# Teensy-Maxuino-Slave-DRV4835.net
KiCad netlist of a schematic drawn in EAGLE
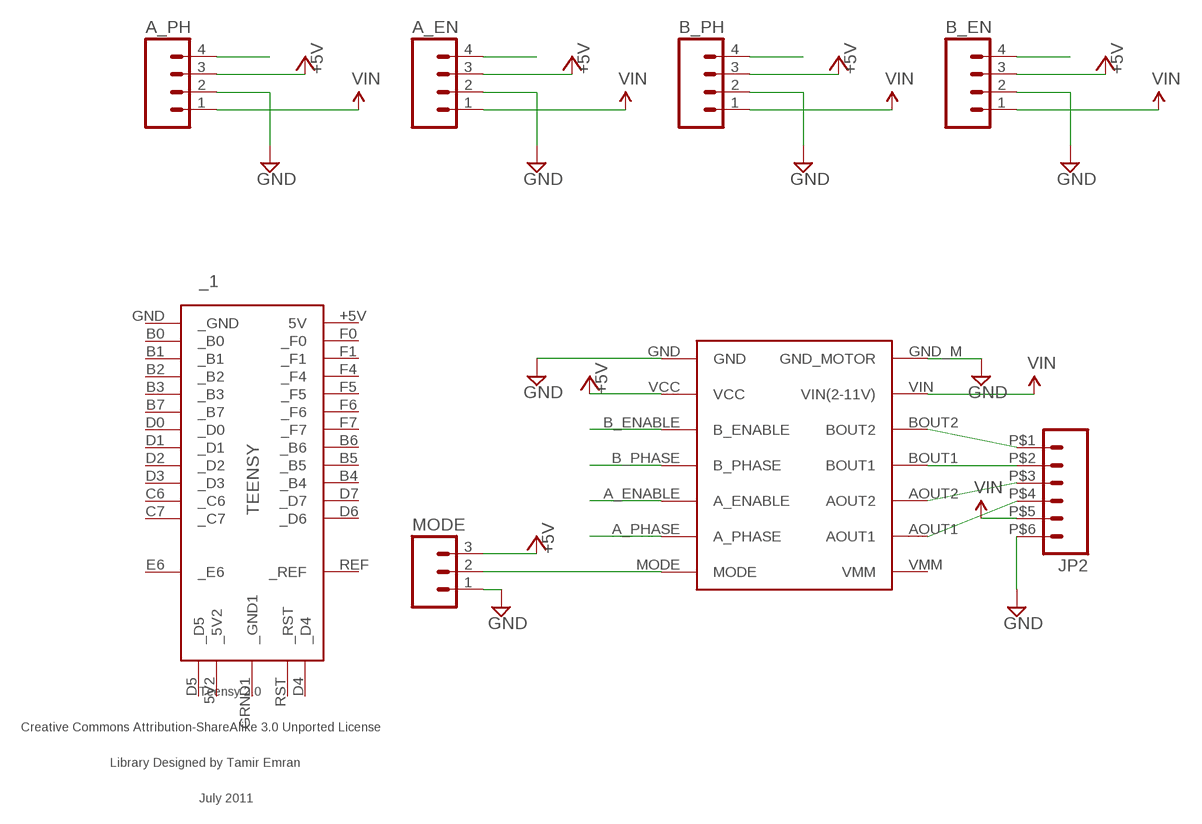
[diagram p0: schematic, sheet 1]

(export (version "E")
  (design (tool "Eeschema 10.0.6"))
  (components
    (comp (ref "A_EN")
      (value "M04PTH")
      (footprint "eagle-import:1X04")
      (libsource (lib "eagle-import") (part "M04PTH"))
    )
    (comp (ref "A_PH")
      (value "M04PTH")
      (footprint "eagle-import:1X04")
      (libsource (lib "eagle-import") (part "M04PTH"))
    )
    (comp (ref "B_EN")
      (value "M04PTH")
      (footprint "eagle-import:1X04")
      (libsource (lib "eagle-import") (part "M04PTH"))
    )
    (comp (ref "B_PH")
      (value "M04PTH")
      (footprint "eagle-import:1X04")
      (libsource (lib "eagle-import") (part "M04PTH"))
    )
    (comp (ref "DRV8835")
      (value "POLOLU_DRV8835")
      (footprint "eagle-import:POLOLU_DRV8835")
      (libsource (lib "eagle-import") (part "POLOLU_DRV8835"))
    )
    (comp (ref "JP2")
      (value "M06")
      (footprint "eagle-import:SPRINGTERMINAL-2.54MM-6")
      (libsource (lib "eagle-import") (part "M06"))
    )
    (comp (ref "MODE")
      (value "M03PTH")
      (footprint "eagle-import:1X03")
      (libsource (lib "eagle-import") (part "M03PTH"))
    )
    (comp (ref "_1")
      (value "TEENSY")
      (footprint "eagle-import:TEENSY")
      (libsource (lib "eagle-import") (part "TEENSY"))
    )
  )
  (nets
    (net (code "1") (name "+5V") (class "Default")
      (node (ref "A_EN") (pin "3") (pinfunction "3_3") (pintype "passive"))
      (node (ref "A_PH") (pin "3") (pinfunction "3_3") (pintype "passive"))
      (node (ref "B_EN") (pin "3") (pinfunction "3_3") (pintype "passive"))
      (node (ref "B_PH") (pin "3") (pinfunction "3_3") (pintype "passive"))
      (node (ref "DRV8835") (pin "VCC") (pinfunction "VCC_VCC") (pintype "bidirectional"))
      (node (ref "MODE") (pin "3") (pinfunction "3_3") (pintype "passive"))
    )
    (net (code "2") (name "/A-ENABLE") (class "Default")
      (node (ref "A_EN") (pin "4") (pinfunction "4_4") (pintype "passive"))
      (node (ref "DRV8835") (pin "A_ENABLE") (pinfunction "A_ENABLE_A_ENABLE") (pintype "bidirectional"))
    )
    (net (code "3") (name "/A-PHASE") (class "Default")
      (node (ref "A_PH") (pin "4") (pinfunction "4_4") (pintype "passive"))
      (node (ref "DRV8835") (pin "A_PHASE") (pinfunction "A_PHASE_A_PHASE") (pintype "bidirectional"))
    )
    (net (code "4") (name "/B-ENABLE") (class "Default")
      (node (ref "B_EN") (pin "4") (pinfunction "4_4") (pintype "passive"))
      (node (ref "DRV8835") (pin "B_ENABLE") (pinfunction "B_ENABLE_B_ENABLE") (pintype "bidirectional"))
    )
    (net (code "5") (name "/B-PHASE") (class "Default")
      (node (ref "B_PH") (pin "4") (pinfunction "4_4") (pintype "passive"))
      (node (ref "DRV8835") (pin "B_PHASE") (pinfunction "B_PHASE_B_PHASE") (pintype "bidirectional"))
    )
    (net (code "6") (name "GND") (class "Default")
      (node (ref "A_EN") (pin "2") (pinfunction "2_2") (pintype "passive"))
      (node (ref "A_PH") (pin "2") (pinfunction "2_2") (pintype "passive"))
      (node (ref "B_EN") (pin "2") (pinfunction "2_2") (pintype "passive"))
      (node (ref "B_PH") (pin "2") (pinfunction "2_2") (pintype "passive"))
      (node (ref "DRV8835") (pin "GND") (pinfunction "GND_GND") (pintype "bidirectional"))
      (node (ref "DRV8835") (pin "GND_M") (pinfunction "GND_MOTOR_GND_M") (pintype "bidirectional"))
      (node (ref "JP2") (pin "P$6") (pinfunction "6_P$6") (pintype "passive"))
      (node (ref "MODE") (pin "1") (pinfunction "1_1") (pintype "passive"))
    )
    (net (code "7") (name "Net-(DRV8835-PadMODE)") (class "Default")
      (node (ref "DRV8835") (pin "MODE") (pinfunction "MODE_MODE") (pintype "bidirectional"))
      (node (ref "MODE") (pin "2") (pinfunction "2_2") (pintype "passive"))
    )
    (net (code "8") (name "Net-(JP2-1)") (class "Default")
      (node (ref "DRV8835") (pin "BOUT2") (pinfunction "BOUT2_BOUT2") (pintype "bidirectional"))
      (node (ref "JP2") (pin "P$1") (pinfunction "1_P$1") (pintype "passive"))
    )
    (net (code "9") (name "Net-(JP2-2)") (class "Default")
      (node (ref "DRV8835") (pin "BOUT1") (pinfunction "BOUT1_BOUT1") (pintype "bidirectional"))
      (node (ref "JP2") (pin "P$2") (pinfunction "2_P$2") (pintype "passive"))
    )
    (net (code "10") (name "Net-(JP2-3)") (class "Default")
      (node (ref "DRV8835") (pin "AOUT2") (pinfunction "AOUT2_AOUT2") (pintype "bidirectional"))
      (node (ref "JP2") (pin "P$3") (pinfunction "3_P$3") (pintype "passive"))
    )
    (net (code "11") (name "Net-(JP2-4)") (class "Default")
      (node (ref "DRV8835") (pin "AOUT1") (pinfunction "AOUT1_AOUT1") (pintype "bidirectional"))
      (node (ref "JP2") (pin "P$4") (pinfunction "4_P$4") (pintype "passive"))
    )
    (net (code "12") (name "VIN") (class "Default")
      (node (ref "A_EN") (pin "1") (pinfunction "1_1") (pintype "passive"))
      (node (ref "A_PH") (pin "1") (pinfunction "1_1") (pintype "passive"))
      (node (ref "B_EN") (pin "1") (pinfunction "1_1") (pintype "passive"))
      (node (ref "B_PH") (pin "1") (pinfunction "1_1") (pintype "passive"))
      (node (ref "DRV8835") (pin "VIN") (pinfunction "VIN(2-11V)_VIN") (pintype "bidirectional"))
      (node (ref "JP2") (pin "P$5") (pinfunction "5_P$5") (pintype "passive"))
    )
    (net (code "13") (name "unconnected-(DRV8835-PadVMM)") (class "Default")
      (node (ref "DRV8835") (pin "VMM") (pinfunction "VMM_VMM") (pintype "bidirectional"))
    )
    (net (code "14") (name "unconnected-(_1-5V-Pad+5V)") (class "Default")
      (node (ref "_1") (pin "+5V") (pinfunction "5V_+5V") (pintype "bidirectional"))
    )
    (net (code "15") (name "unconnected-(_1-_5V2-Pad5V2)") (class "Default")
      (node (ref "_1") (pin "5V2") (pinfunction "_5V2_5V2") (pintype "bidirectional"))
    )
    (net (code "16") (name "unconnected-(_1-_B0-PadB0)") (class "Default")
      (node (ref "_1") (pin "B0") (pinfunction "_B0_B0") (pintype "bidirectional"))
    )
    (net (code "17") (name "unconnected-(_1-_B1-PadB1)") (class "Default")
      (node (ref "_1") (pin "B1") (pinfunction "_B1_B1") (pintype "bidirectional"))
    )
    (net (code "18") (name "unconnected-(_1-_B2-PadB2)") (class "Default")
      (node (ref "_1") (pin "B2") (pinfunction "_B2_B2") (pintype "bidirectional"))
    )
    (net (code "19") (name "unconnected-(_1-_B3-PadB3)") (class "Default")
      (node (ref "_1") (pin "B3") (pinfunction "_B3_B3") (pintype "bidirectional"))
    )
    (net (code "20") (name "unconnected-(_1-_B4-PadB4)") (class "Default")
      (node (ref "_1") (pin "B4") (pinfunction "_B4_B4") (pintype "bidirectional"))
    )
    (net (code "21") (name "unconnected-(_1-_B5-PadB5)") (class "Default")
      (node (ref "_1") (pin "B5") (pinfunction "_B5_B5") (pintype "bidirectional"))
    )
    (net (code "22") (name "unconnected-(_1-_B6-PadB6)") (class "Default")
      (node (ref "_1") (pin "B6") (pinfunction "_B6_B6") (pintype "bidirectional"))
    )
    (net (code "23") (name "unconnected-(_1-_B7-PadB7)") (class "Default")
      (node (ref "_1") (pin "B7") (pinfunction "_B7_B7") (pintype "bidirectional"))
    )
    (net (code "24") (name "unconnected-(_1-_C6-PadC6)") (class "Default")
      (node (ref "_1") (pin "C6") (pinfunction "_C6_C6") (pintype "bidirectional"))
    )
    (net (code "25") (name "unconnected-(_1-_C7-PadC7)") (class "Default")
      (node (ref "_1") (pin "C7") (pinfunction "_C7_C7") (pintype "bidirectional"))
    )
    (net (code "26") (name "unconnected-(_1-_D0-PadD0)") (class "Default")
      (node (ref "_1") (pin "D0") (pinfunction "_D0_D0") (pintype "bidirectional"))
    )
    (net (code "27") (name "unconnected-(_1-_D1-PadD1)") (class "Default")
      (node (ref "_1") (pin "D1") (pinfunction "_D1_D1") (pintype "bidirectional"))
    )
    (net (code "28") (name "unconnected-(_1-_D2-PadD2)") (class "Default")
      (node (ref "_1") (pin "D2") (pinfunction "_D2_D2") (pintype "bidirectional"))
    )
    (net (code "29") (name "unconnected-(_1-_D3-PadD3)") (class "Default")
      (node (ref "_1") (pin "D3") (pinfunction "_D3_D3") (pintype "bidirectional"))
    )
    (net (code "30") (name "unconnected-(_1-_D4-PadD4)") (class "Default")
      (node (ref "_1") (pin "D4") (pinfunction "_D4_D4") (pintype "bidirectional"))
    )
    (net (code "31") (name "unconnected-(_1-_D5-PadD5)") (class "Default")
      (node (ref "_1") (pin "D5") (pinfunction "_D5_D5") (pintype "bidirectional"))
    )
    (net (code "32") (name "unconnected-(_1-_D6-PadD6)") (class "Default")
      (node (ref "_1") (pin "D6") (pinfunction "_D6_D6") (pintype "bidirectional"))
    )
    (net (code "33") (name "unconnected-(_1-_D7-PadD7)") (class "Default")
      (node (ref "_1") (pin "D7") (pinfunction "_D7_D7") (pintype "bidirectional"))
    )
    (net (code "34") (name "unconnected-(_1-_E6-PadE6)") (class "Default")
      (node (ref "_1") (pin "E6") (pinfunction "_E6_E6") (pintype "bidirectional"))
    )
    (net (code "35") (name "unconnected-(_1-_F0-PadF0)") (class "Default")
      (node (ref "_1") (pin "F0") (pinfunction "_F0_F0") (pintype "bidirectional"))
    )
    (net (code "36") (name "unconnected-(_1-_F1-PadF1)") (class "Default")
      (node (ref "_1") (pin "F1") (pinfunction "_F1_F1") (pintype "bidirectional"))
    )
    (net (code "37") (name "unconnected-(_1-_F4-PadF4)") (class "Default")
      (node (ref "_1") (pin "F4") (pinfunction "_F4_F4") (pintype "bidirectional"))
    )
    (net (code "38") (name "unconnected-(_1-_F5-PadF5)") (class "Default")
      (node (ref "_1") (pin "F5") (pinfunction "_F5_F5") (pintype "bidirectional"))
    )
    (net (code "39") (name "unconnected-(_1-_F6-PadF6)") (class "Default")
      (node (ref "_1") (pin "F6") (pinfunction "_F6_F6") (pintype "bidirectional"))
    )
    (net (code "40") (name "unconnected-(_1-_F7-PadF7)") (class "Default")
      (node (ref "_1") (pin "F7") (pinfunction "_F7_F7") (pintype "bidirectional"))
    )
    (net (code "41") (name "unconnected-(_1-_GND-PadGND)") (class "Default")
      (node (ref "_1") (pin "GND") (pinfunction "_GND_GND") (pintype "bidirectional"))
    )
    (net (code "42") (name "unconnected-(_1-_GND1-PadGRND1)") (class "Default")
      (node (ref "_1") (pin "GRND1") (pinfunction "_GND1_GRND1") (pintype "bidirectional"))
    )
    (net (code "43") (name "unconnected-(_1-_REF-PadREF)") (class "Default")
      (node (ref "_1") (pin "REF") (pinfunction "_REF_REF") (pintype "bidirectional"))
    )
    (net (code "44") (name "unconnected-(_1-_RST-PadRST)") (class "Default")
      (node (ref "_1") (pin "RST") (pinfunction "_RST_RST") (pintype "bidirectional"))
    )
  )
)
